# RPL_MCU.net
KiCad netlist of a schematic drawn in Altium Designer
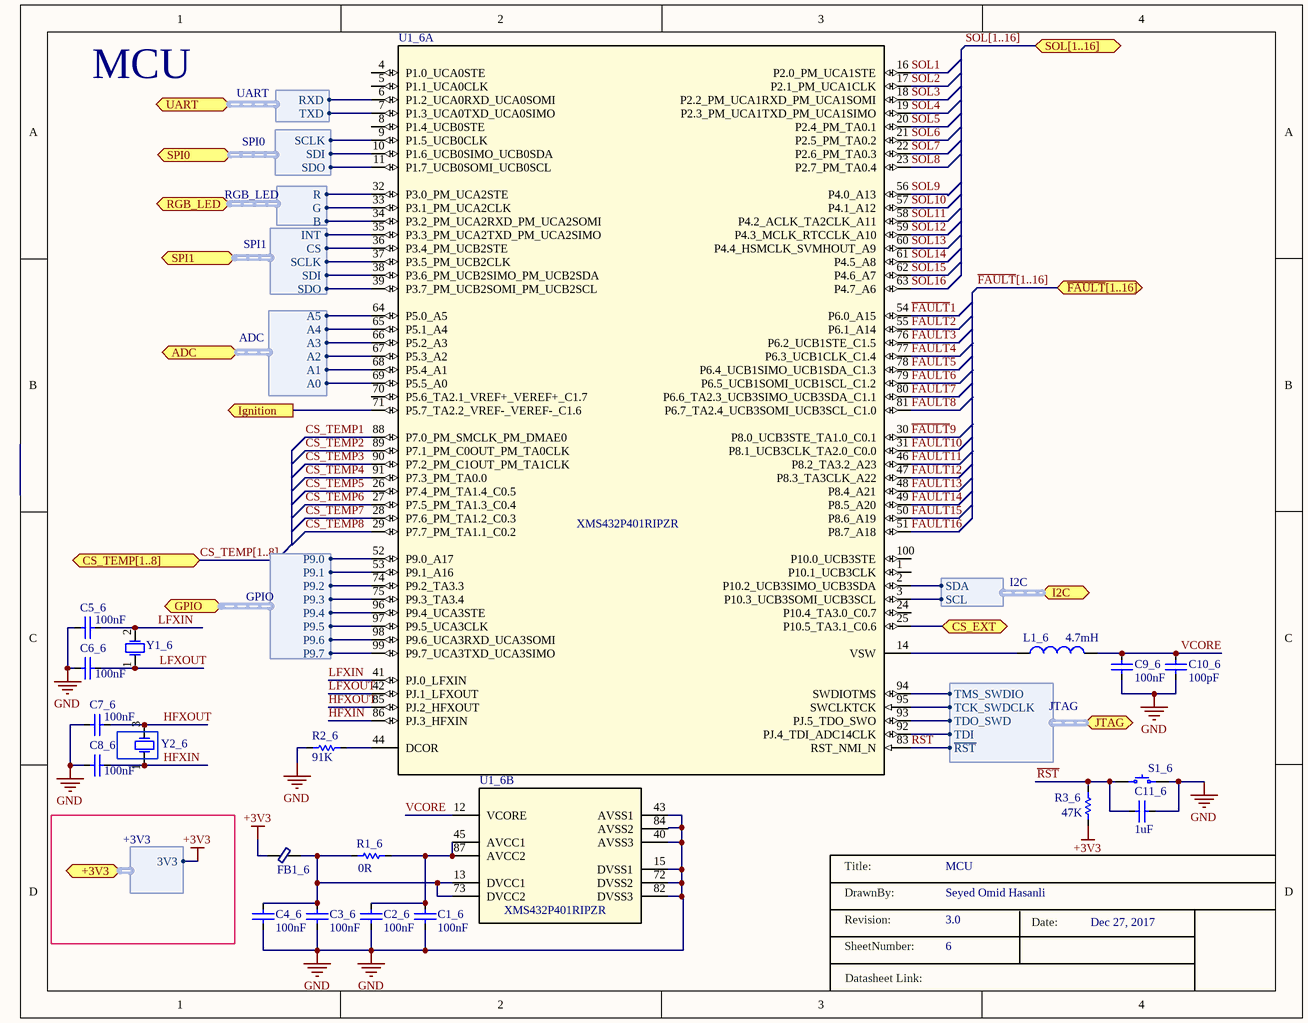
[diagram p0: RPL_MCU.SchDoc]

(export (version "E")
  (design (tool "Eeschema 10.0.6"))
  (components
    (comp (ref "C1_6")
      (value "100nF")
      (footprint "C0805C475K9RACAUTO")
      (fields (field (name "Comment") "Cap"))
      (libsource (lib "Generic_Library") (part "Cap"))
    )
    (comp (ref "C2_6")
      (value "100nF")
      (footprint "C0805C475K9RACAUTO")
      (fields (field (name "Comment") "Cap"))
      (libsource (lib "Generic_Library") (part "Cap"))
    )
    (comp (ref "C3_6")
      (value "100nF")
      (footprint "C0805C475K9RACAUTO")
      (fields (field (name "Comment") "Cap"))
      (libsource (lib "Generic_Library") (part "Cap"))
    )
    (comp (ref "C4_6")
      (value "100nF")
      (footprint "C0805C475K9RACAUTO")
      (fields (field (name "Comment") "Cap"))
      (libsource (lib "Generic_Library") (part "Cap"))
    )
    (comp (ref "C5_6")
      (value "100nF")
      (footprint "C0805C475K9RACAUTO")
      (fields (field (name "Comment") "Cap"))
      (libsource (lib "Generic_Library") (part "Cap"))
    )
    (comp (ref "C6_6")
      (value "100nF")
      (footprint "C0805C475K9RACAUTO")
      (fields (field (name "Comment") "Cap"))
      (libsource (lib "Generic_Library") (part "Cap"))
    )
    (comp (ref "C7_6")
      (value "100nF")
      (footprint "C0805C475K9RACAUTO")
      (fields (field (name "Comment") "Cap"))
      (libsource (lib "Generic_Library") (part "Cap"))
    )
    (comp (ref "C8_6")
      (value "100nF")
      (footprint "C0805C475K9RACAUTO")
      (fields (field (name "Comment") "Cap"))
      (libsource (lib "Generic_Library") (part "Cap"))
    )
    (comp (ref "C9_6")
      (value "100nF")
      (footprint "C0805C475K9RACAUTO")
      (fields (field (name "Comment") "Cap"))
      (libsource (lib "Generic_Library") (part "Cap"))
    )
    (comp (ref "C10_6")
      (value "100pF")
      (footprint "C0805C475K9RACAUTO")
      (fields (field (name "Comment") "Cap"))
      (libsource (lib "Generic_Library") (part "Cap"))
    )
    (comp (ref "C11_6")
      (value "1uF")
      (footprint "C0805C475K9RACAUTO")
      (fields (field (name "Comment") "Cap"))
      (libsource (lib "Generic_Library") (part "Cap"))
    )
    (comp (ref "FB1_6")
      (value "ferrite bead")
      (footprint "RES 0805")
      (libsource (lib "Generic_Library") (part "ferrite bead"))
    )
    (comp (ref "L1_6")
      (value "4.7mH")
      (footprint "INDC2016X95")
      (fields (field (name "Comment") "Inductor"))
      (libsource (lib "Generic_Library") (part "Inductor"))
    )
    (comp (ref "R1_6")
      (value "0R")
      (footprint "RES 0805")
      (fields (field (name "Comment") "Res"))
      (libsource (lib "Generic_Library") (part "Res"))
    )
    (comp (ref "R2_6")
      (value "91K")
      (footprint "RES 0805")
      (fields (field (name "Comment") "Res"))
      (libsource (lib "Generic_Library") (part "Res"))
    )
    (comp (ref "R3_6")
      (value "47K")
      (footprint "RES 0805")
      (fields (field (name "Comment") "Res"))
      (libsource (lib "Generic_Library") (part "Res"))
    )
    (comp (ref "S1_6")
      (value "FSMSMTR")
      (footprint "TE FSMSMTR")
      (description "SWITCH TACTILE SPST-NO 0.05A 24V")
      (fields (field (name "MANUFACTURER") "TE Connectivity Alcoswitch Switches"))
      (libsource (lib "Celestial Library Database") (part "SPST-NO 2 PIN"))
    )
    (comp (ref "U1_6")
      (value "XMS432P401RIPZR")
      (footprint "MSP432P401R:PZ0100A_N")
      (description "Imported")
      (fields (field (name "MANUFACTURER") "Texas Instruments"))
      (libsource (lib "Generic_Library") (part "XMS432P401RIPZR"))
    )
    (comp (ref "Y1_6")
      (value "32.7680KHZ 12.5PF")
      (footprint "XTAL320X150X90")
      (libsource (lib "Generic_Library") (part "XTAL"))
    )
    (comp (ref "Y2_6")
      (value "48.00 MHZ 12.0PF")
      (footprint "OSCSC105P160X120X35-4N")
      (libsource (lib "Generic_Library") (part "XTAL_4pin_16MHz_8pF"))
    )
  )
  (nets
    (net (code "9") (name "+3V3") (class "Default")
      (node (ref "FB1_6") (pin "1") (pinfunction "1_1") (pintype "passive"))
      (node (ref "R3_6") (pin "1") (pinfunction "1_1") (pintype "passive"))
    )
    (net (code "10") (name "/CS_EXT") (class "Default")
      (node (ref "U1_6") (pin "25") (pinfunction "P10.5_TA3.1_C0.6_25") (pintype "bidirectional"))
    )
    (net (code "11") (name "/CS_TEMP1") (class "Default")
      (node (ref "U1_6") (pin "88") (pinfunction "P7.0_PM_SMCLK_PM_DMAE0_88") (pintype "bidirectional"))
    )
    (net (code "12") (name "/CS_TEMP2") (class "Default")
      (node (ref "U1_6") (pin "89") (pinfunction "P7.1_PM_C0OUT_PM_TA0CLK_89") (pintype "bidirectional"))
    )
    (net (code "13") (name "/CS_TEMP3") (class "Default")
      (node (ref "U1_6") (pin "90") (pinfunction "P7.2_PM_C1OUT_PM_TA1CLK_90") (pintype "bidirectional"))
    )
    (net (code "14") (name "/CS_TEMP4") (class "Default")
      (node (ref "U1_6") (pin "91") (pinfunction "P7.3_PM_TA0.0_91") (pintype "bidirectional"))
    )
    (net (code "15") (name "/CS_TEMP5") (class "Default")
      (node (ref "U1_6") (pin "26") (pinfunction "P7.4_PM_TA1.4_C0.5_26") (pintype "bidirectional"))
    )
    (net (code "16") (name "/CS_TEMP6") (class "Default")
      (node (ref "U1_6") (pin "27") (pinfunction "P7.5_PM_TA1.3_C0.4_27") (pintype "bidirectional"))
    )
    (net (code "17") (name "/CS_TEMP7") (class "Default")
      (node (ref "U1_6") (pin "28") (pinfunction "P7.6_PM_TA1.2_C0.3_28") (pintype "bidirectional"))
    )
    (net (code "18") (name "/CS_TEMP8") (class "Default")
      (node (ref "U1_6") (pin "29") (pinfunction "P7.7_PM_TA1.1_C0.2_29") (pintype "bidirectional"))
    )
    (net (code "20") (name "/HFXIN") (class "Default")
      (node (ref "C8_6") (pin "2") (pinfunction "2_2") (pintype "passive"))
      (node (ref "U1_6") (pin "86") (pinfunction "PJ.3_HFXIN_86") (pintype "bidirectional"))
      (node (ref "Y2_6") (pin "1") (pinfunction "OSC1_1") (pintype "passive"))
    )
    (net (code "21") (name "/HFXOUT") (class "Default")
      (node (ref "C7_6") (pin "2") (pinfunction "2_2") (pintype "passive"))
      (node (ref "U1_6") (pin "85") (pinfunction "PJ.2_HFXOUT_85") (pintype "bidirectional"))
      (node (ref "Y2_6") (pin "3") (pinfunction "OSC3_3") (pintype "passive"))
    )
    (net (code "22") (name "/Ignition") (class "Default")
      (node (ref "U1_6") (pin "71") (pinfunction "P5.7_TA2.2_VREF-_VEREF-_C1.6_71") (pintype "bidirectional"))
    )
    (net (code "23") (name "/LFXIN") (class "Default")
      (node (ref "C5_6") (pin "2") (pinfunction "2_2") (pintype "passive"))
      (node (ref "U1_6") (pin "41") (pinfunction "PJ.0_LFXIN_41") (pintype "bidirectional"))
      (node (ref "Y1_6") (pin "2") (pinfunction "OSC2_2") (pintype "passive"))
    )
    (net (code "24") (name "/LFXOUT") (class "Default")
      (node (ref "C6_6") (pin "2") (pinfunction "2_2") (pintype "passive"))
      (node (ref "U1_6") (pin "42") (pinfunction "PJ.1_LFXOUT_42") (pintype "bidirectional"))
      (node (ref "Y1_6") (pin "1") (pinfunction "OSC1_1") (pintype "passive"))
    )
    (net (code "26") (name "/SOL1") (class "Default")
      (node (ref "U1_6") (pin "16") (pinfunction "P2.0_PM_UCA1STE_16") (pintype "bidirectional"))
    )
    (net (code "27") (name "/SOL2") (class "Default")
      (node (ref "U1_6") (pin "17") (pinfunction "P2.1_PM_UCA1CLK_17") (pintype "bidirectional"))
    )
    (net (code "28") (name "/SOL3") (class "Default")
      (node (ref "U1_6") (pin "18") (pinfunction "P2.2_PM_UCA1RXD_PM_UCA1SOMI_18") (pintype "bidirectional"))
    )
    (net (code "29") (name "/SOL4") (class "Default")
      (node (ref "U1_6") (pin "19") (pinfunction "P2.3_PM_UCA1TXD_PM_UCA1SIMO_19") (pintype "bidirectional"))
    )
    (net (code "30") (name "/SOL5") (class "Default")
      (node (ref "U1_6") (pin "20") (pinfunction "P2.4_PM_TA0.1_20") (pintype "bidirectional"))
    )
    (net (code "31") (name "/SOL6") (class "Default")
      (node (ref "U1_6") (pin "21") (pinfunction "P2.5_PM_TA0.2_21") (pintype "bidirectional"))
    )
    (net (code "32") (name "/SOL7") (class "Default")
      (node (ref "U1_6") (pin "22") (pinfunction "P2.6_PM_TA0.3_22") (pintype "bidirectional"))
    )
    (net (code "33") (name "/SOL8") (class "Default")
      (node (ref "U1_6") (pin "23") (pinfunction "P2.7_PM_TA0.4_23") (pintype "bidirectional"))
    )
    (net (code "34") (name "/SOL9") (class "Default")
      (node (ref "U1_6") (pin "56") (pinfunction "P4.0_A13_56") (pintype "bidirectional"))
    )
    (net (code "35") (name "/SOL10") (class "Default")
      (node (ref "U1_6") (pin "57") (pinfunction "P4.1_A12_57") (pintype "bidirectional"))
    )
    (net (code "36") (name "/SOL11") (class "Default")
      (node (ref "U1_6") (pin "58") (pinfunction "P4.2_ACLK_TA2CLK_A11_58") (pintype "bidirectional"))
    )
    (net (code "37") (name "/SOL12") (class "Default")
      (node (ref "U1_6") (pin "59") (pinfunction "P4.3_MCLK_RTCCLK_A10_59") (pintype "bidirectional"))
    )
    (net (code "38") (name "/SOL13") (class "Default")
      (node (ref "U1_6") (pin "60") (pinfunction "P4.4_HSMCLK_SVMHOUT_A9_60") (pintype "bidirectional"))
    )
    (net (code "39") (name "/SOL14") (class "Default")
      (node (ref "U1_6") (pin "61") (pinfunction "P4.5_A8_61") (pintype "bidirectional"))
    )
    (net (code "40") (name "/SOL15") (class "Default")
      (node (ref "U1_6") (pin "62") (pinfunction "P4.6_A7_62") (pintype "bidirectional"))
    )
    (net (code "41") (name "/SOL16") (class "Default")
      (node (ref "U1_6") (pin "63") (pinfunction "P4.7_A6_63") (pintype "bidirectional"))
    )
    (net (code "43") (name "/VCORE") (class "Default")
      (node (ref "C10_6") (pin "2") (pinfunction "2_2") (pintype "passive"))
      (node (ref "C9_6") (pin "2") (pinfunction "2_2") (pintype "passive"))
      (node (ref "L1_6") (pin "2") (pinfunction "2_2") (pintype "passive"))
      (node (ref "U1_6") (pin "12") (pinfunction "VCORE_12") (pintype "power_in"))
    )
    (net (code "52") (name "/~{FAULT}1") (class "Default")
      (node (ref "U1_6") (pin "54") (pinfunction "P6.0_A15_54") (pintype "bidirectional"))
    )
    (net (code "53") (name "/~{FAULT}2") (class "Default")
      (node (ref "U1_6") (pin "55") (pinfunction "P6.1_A14_55") (pintype "bidirectional"))
    )
    (net (code "54") (name "/~{FAULT}3") (class "Default")
      (node (ref "U1_6") (pin "76") (pinfunction "P6.2_UCB1STE_C1.5_76") (pintype "bidirectional"))
    )
    (net (code "55") (name "/~{FAULT}4") (class "Default")
      (node (ref "U1_6") (pin "77") (pinfunction "P6.3_UCB1CLK_C1.4_77") (pintype "bidirectional"))
    )
    (net (code "56") (name "/~{FAULT}5") (class "Default")
      (node (ref "U1_6") (pin "78") (pinfunction "P6.4_UCB1SIMO_UCB1SDA_C1.3_78") (pintype "bidirectional"))
    )
    (net (code "57") (name "/~{FAULT}6") (class "Default")
      (node (ref "U1_6") (pin "79") (pinfunction "P6.5_UCB1SOMI_UCB1SCL_C1.2_79") (pintype "bidirectional"))
    )
    (net (code "58") (name "/~{FAULT}7") (class "Default")
      (node (ref "U1_6") (pin "80") (pinfunction "P6.6_TA2.3_UCB3SIMO_UCB3SDA_C1.1_80") (pintype "bidirectional"))
    )
    (net (code "59") (name "/~{FAULT}8") (class "Default")
      (node (ref "U1_6") (pin "81") (pinfunction "P6.7_TA2.4_UCB3SOMI_UCB3SCL_C1.0_81") (pintype "bidirectional"))
    )
    (net (code "60") (name "/~{FAULT}9") (class "Default")
      (node (ref "U1_6") (pin "30") (pinfunction "P8.0_UCB3STE_TA1.0_C0.1_30") (pintype "bidirectional"))
    )
    (net (code "61") (name "/~{FAULT}10") (class "Default")
      (node (ref "U1_6") (pin "31") (pinfunction "P8.1_UCB3CLK_TA2.0_C0.0_31") (pintype "bidirectional"))
    )
    (net (code "62") (name "/~{FAULT}11") (class "Default")
      (node (ref "U1_6") (pin "46") (pinfunction "P8.2_TA3.2_A23_46") (pintype "bidirectional"))
    )
    (net (code "63") (name "/~{FAULT}12") (class "Default")
      (node (ref "U1_6") (pin "47") (pinfunction "P8.3_TA3CLK_A22_47") (pintype "bidirectional"))
    )
    (net (code "64") (name "/~{FAULT}13") (class "Default")
      (node (ref "U1_6") (pin "48") (pinfunction "P8.4_A21_48") (pintype "bidirectional"))
    )
    (net (code "65") (name "/~{FAULT}14") (class "Default")
      (node (ref "U1_6") (pin "49") (pinfunction "P8.5_A20_49") (pintype "bidirectional"))
    )
    (net (code "66") (name "/~{FAULT}15") (class "Default")
      (node (ref "U1_6") (pin "50") (pinfunction "P8.6_A19_50") (pintype "bidirectional"))
    )
    (net (code "67") (name "/~{FAULT}16") (class "Default")
      (node (ref "U1_6") (pin "51") (pinfunction "P8.7_A18_51") (pintype "bidirectional"))
    )
    (net (code "69") (name "/~{RST}") (class "Default")
      (node (ref "C11_6") (pin "1") (pinfunction "1_1") (pintype "passive"))
      (node (ref "R3_6") (pin "2") (pinfunction "2_2") (pintype "passive"))
      (node (ref "S1_6") (pin "1") (pinfunction "1_1") (pintype "passive"))
      (node (ref "U1_6") (pin "83") (pinfunction "RST_NMI_N_83") (pintype "input"))
    )
    (net (code "70") (name "GND") (class "Default")
      (node (ref "C10_6") (pin "1") (pinfunction "1_1") (pintype "passive"))
      (node (ref "C11_6") (pin "2") (pinfunction "2_2") (pintype "passive"))
      (node (ref "C1_6") (pin "1") (pinfunction "1_1") (pintype "passive"))
      (node (ref "C2_6") (pin "1") (pinfunction "1_1") (pintype "passive"))
      (node (ref "C3_6") (pin "1") (pinfunction "1_1") (pintype "passive"))
      (node (ref "C4_6") (pin "1") (pinfunction "1_1") (pintype "passive"))
      (node (ref "C5_6") (pin "1") (pinfunction "1_1") (pintype "passive"))
      (node (ref "C6_6") (pin "1") (pinfunction "1_1") (pintype "passive"))
      (node (ref "C7_6") (pin "1") (pinfunction "1_1") (pintype "passive"))
      (node (ref "C8_6") (pin "1") (pinfunction "1_1") (pintype "passive"))
      (node (ref "C9_6") (pin "1") (pinfunction "1_1") (pintype "passive"))
      (node (ref "R2_6") (pin "1") (pinfunction "1_1") (pintype "passive"))
      (node (ref "S1_6") (pin "2") (pinfunction "2_2") (pintype "passive"))
      (node (ref "U1_6") (pin "15") (pinfunction "DVSS1_15") (pintype "power_in"))
      (node (ref "U1_6") (pin "40") (pinfunction "AVSS3_40") (pintype "power_in"))
      (node (ref "U1_6") (pin "43") (pinfunction "AVSS1_43") (pintype "power_in"))
      (node (ref "U1_6") (pin "72") (pinfunction "DVSS2_72") (pintype "power_in"))
      (node (ref "U1_6") (pin "82") (pinfunction "DVSS3_82") (pintype "power_in"))
    )
    (net (code "71") (name "Net-(U1_6A-DCOR)") (class "Default")
      (node (ref "R2_6") (pin "2") (pinfunction "2_2") (pintype "passive"))
      (node (ref "U1_6") (pin "44") (pinfunction "DCOR_44") (pintype "passive"))
    )
    (net (code "72") (name "Net-(U1_6A-VSW)") (class "Default")
      (node (ref "L1_6") (pin "1") (pinfunction "1_1") (pintype "passive"))
      (node (ref "U1_6") (pin "14") (pinfunction "VSW_14") (pintype "passive"))
    )
    (net (code "73") (name "Net-(U1_6B-AVCC1)") (class "Default")
      (node (ref "C1_6") (pin "2") (pinfunction "2_2") (pintype "passive"))
      (node (ref "C2_6") (pin "2") (pinfunction "2_2") (pintype "passive"))
      (node (ref "R1_6") (pin "2") (pinfunction "2_2") (pintype "passive"))
      (node (ref "U1_6") (pin "45") (pinfunction "AVCC1_45") (pintype "power_in"))
      (node (ref "U1_6") (pin "87") (pinfunction "AVCC2_87") (pintype "power_in"))
    )
    (net (code "74") (name "Net-(U1_6B-DVCC1)") (class "Default")
      (node (ref "C3_6") (pin "2") (pinfunction "2_2") (pintype "passive"))
      (node (ref "C4_6") (pin "2") (pinfunction "2_2") (pintype "passive"))
      (node (ref "FB1_6") (pin "2") (pinfunction "2_2") (pintype "passive"))
      (node (ref "R1_6") (pin "1") (pinfunction "1_1") (pintype "passive"))
      (node (ref "U1_6") (pin "13") (pinfunction "DVCC1_13") (pintype "power_in"))
      (node (ref "U1_6") (pin "73") (pinfunction "DVCC2_73") (pintype "power_in"))
    )
    (net (code "75") (name "unconnected-(U1_6A-P1.0_UCA0STE-Pad4)") (class "Default")
      (node (ref "U1_6") (pin "4") (pinfunction "P1.0_UCA0STE_4") (pintype "bidirectional"))
    )
    (net (code "76") (name "unconnected-(U1_6A-P1.1_UCA0CLK-Pad5)") (class "Default")
      (node (ref "U1_6") (pin "5") (pinfunction "P1.1_UCA0CLK_5") (pintype "bidirectional"))
    )
    (net (code "77") (name "unconnected-(U1_6A-P1.2_UCA0RXD_UCA0SOMI-Pad6)") (class "Default")
      (node (ref "U1_6") (pin "6") (pinfunction "P1.2_UCA0RXD_UCA0SOMI_6") (pintype "bidirectional"))
    )
    (net (code "78") (name "unconnected-(U1_6A-P1.3_UCA0TXD_UCA0SIMO-Pad7)") (class "Default")
      (node (ref "U1_6") (pin "7") (pinfunction "P1.3_UCA0TXD_UCA0SIMO_7") (pintype "bidirectional"))
    )
    (net (code "79") (name "unconnected-(U1_6A-P1.4_UCB0STE-Pad8)") (class "Default")
      (node (ref "U1_6") (pin "8") (pinfunction "P1.4_UCB0STE_8") (pintype "bidirectional"))
    )
    (net (code "80") (name "unconnected-(U1_6A-P1.5_UCB0CLK-Pad9)") (class "Default")
      (node (ref "U1_6") (pin "9") (pinfunction "P1.5_UCB0CLK_9") (pintype "bidirectional"))
    )
    (net (code "81") (name "unconnected-(U1_6A-P1.6_UCB0SIMO_UCB0SDA-Pad10)") (class "Default")
      (node (ref "U1_6") (pin "10") (pinfunction "P1.6_UCB0SIMO_UCB0SDA_10") (pintype "bidirectional"))
    )
    (net (code "82") (name "unconnected-(U1_6A-P1.7_UCB0SOMI_UCB0SCL-Pad11)") (class "Default")
      (node (ref "U1_6") (pin "11") (pinfunction "P1.7_UCB0SOMI_UCB0SCL_11") (pintype "bidirectional"))
    )
    (net (code "83") (name "unconnected-(U1_6A-P3.0_PM_UCA2STE-Pad32)") (class "Default")
      (node (ref "U1_6") (pin "32") (pinfunction "P3.0_PM_UCA2STE_32") (pintype "bidirectional"))
    )
    (net (code "84") (name "unconnected-(U1_6A-P3.1_PM_UCA2CLK-Pad33)") (class "Default")
      (node (ref "U1_6") (pin "33") (pinfunction "P3.1_PM_UCA2CLK_33") (pintype "bidirectional"))
    )
    (net (code "85") (name "unconnected-(U1_6A-P3.2_PM_UCA2RXD_PM_UCA2SOMI-Pad34)") (class "Default")
      (node (ref "U1_6") (pin "34") (pinfunction "P3.2_PM_UCA2RXD_PM_UCA2SOMI_34") (pintype "bidirectional"))
    )
    (net (code "86") (name "unconnected-(U1_6A-P3.3_PM_UCA2TXD_PM_UCA2SIMO-Pad35)") (class "Default")
      (node (ref "U1_6") (pin "35") (pinfunction "P3.3_PM_UCA2TXD_PM_UCA2SIMO_35") (pintype "bidirectional"))
    )
    (net (code "87") (name "unconnected-(U1_6A-P3.4_PM_UCB2STE-Pad36)") (class "Default")
      (node (ref "U1_6") (pin "36") (pinfunction "P3.4_PM_UCB2STE_36") (pintype "bidirectional"))
    )
    (net (code "88") (name "unconnected-(U1_6A-P3.5_PM_UCB2CLK-Pad37)") (class "Default")
      (node (ref "U1_6") (pin "37") (pinfunction "P3.5_PM_UCB2CLK_37") (pintype "bidirectional"))
    )
    (net (code "89") (name "unconnected-(U1_6A-P3.6_PM_UCB2SIMO_PM_UCB2SDA-Pad38)") (class "Default")
      (node (ref "U1_6") (pin "38") (pinfunction "P3.6_PM_UCB2SIMO_PM_UCB2SDA_38") (pintype "bidirectional"))
    )
    (net (code "90") (name "unconnected-(U1_6A-P3.7_PM_UCB2SOMI_PM_UCB2SCL-Pad39)") (class "Default")
      (node (ref "U1_6") (pin "39") (pinfunction "P3.7_PM_UCB2SOMI_PM_UCB2SCL_39") (pintype "bidirectional"))
    )
    (net (code "91") (name "unconnected-(U1_6A-P5.0_A5-Pad64)") (class "Default")
      (node (ref "U1_6") (pin "64") (pinfunction "P5.0_A5_64") (pintype "bidirectional"))
    )
    (net (code "92") (name "unconnected-(U1_6A-P5.1_A4-Pad65)") (class "Default")
      (node (ref "U1_6") (pin "65") (pinfunction "P5.1_A4_65") (pintype "bidirectional"))
    )
    (net (code "93") (name "unconnected-(U1_6A-P5.2_A3-Pad66)") (class "Default")
      (node (ref "U1_6") (pin "66") (pinfunction "P5.2_A3_66") (pintype "bidirectional"))
    )
    (net (code "94") (name "unconnected-(U1_6A-P5.3_A2-Pad67)") (class "Default")
      (node (ref "U1_6") (pin "67") (pinfunction "P5.3_A2_67") (pintype "bidirectional"))
    )
    (net (code "95") (name "unconnected-(U1_6A-P5.4_A1-Pad68)") (class "Default")
      (node (ref "U1_6") (pin "68") (pinfunction "P5.4_A1_68") (pintype "bidirectional"))
    )
    (net (code "96") (name "unconnected-(U1_6A-P5.5_A0-Pad69)") (class "Default")
      (node (ref "U1_6") (pin "69") (pinfunction "P5.5_A0_69") (pintype "bidirectional"))
    )
    (net (code "97") (name "unconnected-(U1_6A-P5.6_TA2.1_VREF+_VEREF+_C1.7-Pad70)") (class "Default")
      (node (ref "U1_6") (pin "70") (pinfunction "P5.6_TA2.1_VREF+_VEREF+_C1.7_70") (pintype "bidirectional"))
    )
    (net (code "98") (name "unconnected-(U1_6A-P9.0_A17-Pad52)") (class "Default")
      (node (ref "U1_6") (pin "52") (pinfunction "P9.0_A17_52") (pintype "bidirectional"))
    )
    (net (code "99") (name "unconnected-(U1_6A-P9.1_A16-Pad53)") (class "Default")
      (node (ref "U1_6") (pin "53") (pinfunction "P9.1_A16_53") (pintype "bidirectional"))
    )
    (net (code "100") (name "unconnected-(U1_6A-P9.2_TA3.3-Pad74)") (class "Default")
      (node (ref "U1_6") (pin "74") (pinfunction "P9.2_TA3.3_74") (pintype "bidirectional"))
    )
    (net (code "101") (name "unconnected-(U1_6A-P9.3_TA3.4-Pad75)") (class "Default")
      (node (ref "U1_6") (pin "75") (pinfunction "P9.3_TA3.4_75") (pintype "bidirectional"))
    )
    (net (code "102") (name "unconnected-(U1_6A-P9.4_UCA3STE-Pad96)") (class "Default")
      (node (ref "U1_6") (pin "96") (pinfunction "P9.4_UCA3STE_96") (pintype "bidirectional"))
    )
    (net (code "103") (name "unconnected-(U1_6A-P9.5_UCA3CLK-Pad97)") (class "Default")
      (node (ref "U1_6") (pin "97") (pinfunction "P9.5_UCA3CLK_97") (pintype "bidirectional"))
    )
    (net (code "104") (name "unconnected-(U1_6A-P9.6_UCA3RXD_UCA3SOMI-Pad98)") (class "Default")
      (node (ref "U1_6") (pin "98") (pinfunction "P9.6_UCA3RXD_UCA3SOMI_98") (pintype "bidirectional"))
    )
    (net (code "105") (name "unconnected-(U1_6A-P9.7_UCA3TXD_UCA3SIMO-Pad99)") (class "Default")
      (node (ref "U1_6") (pin "99") (pinfunction "P9.7_UCA3TXD_UCA3SIMO_99") (pintype "bidirectional"))
    )
    (net (code "106") (name "unconnected-(U1_6A-P10.0_UCB3STE-Pad100)") (class "Default")
      (node (ref "U1_6") (pin "100") (pinfunction "P10.0_UCB3STE_100") (pintype "bidirectional"))
    )
    (net (code "107") (name "unconnected-(U1_6A-P10.1_UCB3CLK-Pad1)") (class "Default")
      (node (ref "U1_6") (pin "1") (pinfunction "P10.1_UCB3CLK_1") (pintype "bidirectional"))
    )
    (net (code "108") (name "unconnected-(U1_6A-P10.2_UCB3SIMO_UCB3SDA-Pad2)") (class "Default")
      (node (ref "U1_6") (pin "2") (pinfunction "P10.2_UCB3SIMO_UCB3SDA_2") (pintype "bidirectional"))
    )
    (net (code "109") (name "unconnected-(U1_6A-P10.3_UCB3SOMI_UCB3SCL-Pad3)") (class "Default")
      (node (ref "U1_6") (pin "3") (pinfunction "P10.3_UCB3SOMI_UCB3SCL_3") (pintype "bidirectional"))
    )
    (net (code "110") (name "unconnected-(U1_6A-P10.4_TA3.0_C0.7-Pad24)") (class "Default")
      (node (ref "U1_6") (pin "24") (pinfunction "P10.4_TA3.0_C0.7_24") (pintype "bidirectional"))
    )
    (net (code "111") (name "unconnected-(U1_6A-PJ.4_TDI_ADC14CLK-Pad92)") (class "Default")
      (node (ref "U1_6") (pin "92") (pinfunction "PJ.4_TDI_ADC14CLK_92") (pintype "bidirectional"))
    )
    (net (code "112") (name "unconnected-(U1_6A-PJ.5_TDO_SWO-Pad93)") (class "Default")
      (node (ref "U1_6") (pin "93") (pinfunction "PJ.5_TDO_SWO_93") (pintype "bidirectional"))
    )
    (net (code "113") (name "unconnected-(U1_6A-SWCLKTCK-Pad95)") (class "Default")
      (node (ref "U1_6") (pin "95") (pinfunction "SWCLKTCK_95") (pintype "input"))
    )
    (net (code "114") (name "unconnected-(U1_6A-SWDIOTMS-Pad94)") (class "Default")
      (node (ref "U1_6") (pin "94") (pinfunction "SWDIOTMS_94") (pintype "bidirectional"))
    )
    (net (code "115") (name "unconnected-(U1_6B-AVSS2-Pad84)") (class "Default")
      (node (ref "U1_6") (pin "84") (pinfunction "AVSS2_84") (pintype "power_in"))
    )
    (net (code "116") (name "unconnected-(Y2_6-OSC2-Pad2)") (class "Default")
      (node (ref "Y2_6") (pin "2") (pinfunction "OSC2_2") (pintype "passive"))
    )
    (net (code "117") (name "unconnected-(Y2_6-OSC4-Pad4)") (class "Default")
      (node (ref "Y2_6") (pin "4") (pinfunction "OSC4_4") (pintype "passive"))
    )
  )
)
